# 1_WiFi_POWER.net
KiCad netlist of a schematic drawn in Altium Designer
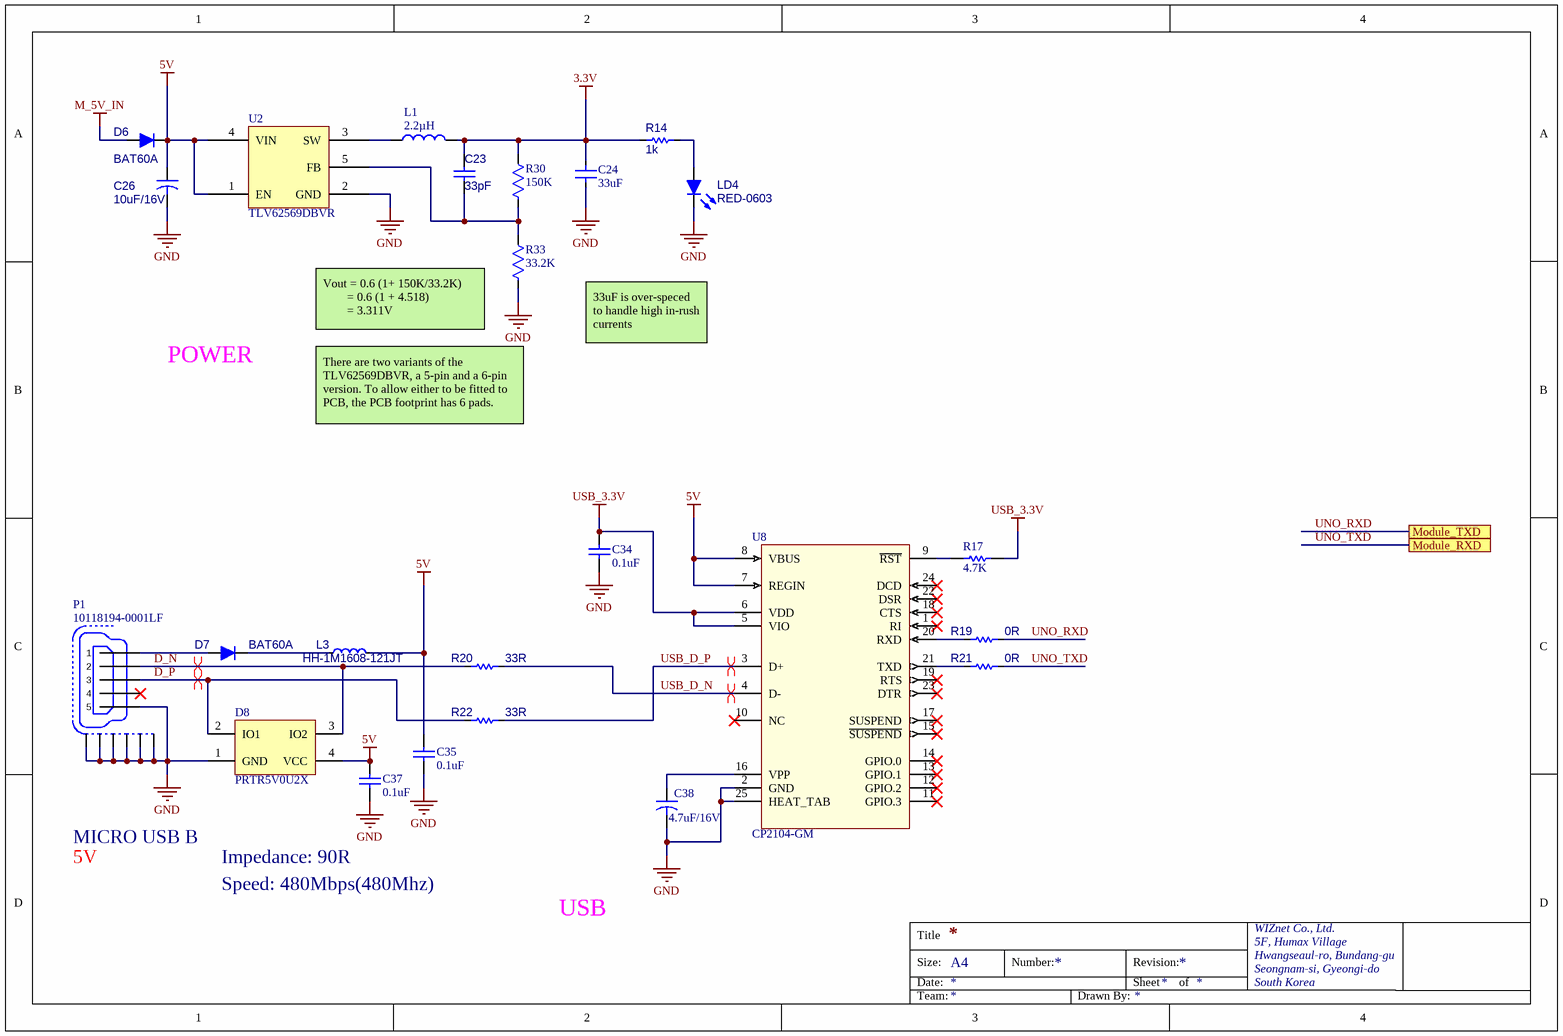
[diagram p0: 1.WiFi_POWER.SchDoc]

(export (version "E")
  (design (tool "Eeschema 10.0.6"))
  (components
    (comp (ref "C23")
      (value "33pF")
      (footprint "CAP-0402")
      (description "Ceramic CAP 0402(1005)")
      (libsource (lib "Scott_lib") (part "CAP-0402"))
    )
    (comp (ref "C24")
      (value "33uF")
      (footprint "CAP-0805")
      (description "0805 10V 33uF X5R 20%")
      (fields
        (field (name "MANUFACTURER") "TDK")
        (field (name "MANUFACTURER PART NUMBER") "C2012X5R0J336M125AC")
      )
      (libsource (lib "TDK_Capacitor_C_0805") (part "33uF 0805 X5R 6.3V"))
    )
    (comp (ref "C26")
      (value "10uF/16V")
      (footprint "CAP-A Size")
      (description "Tantal CAP A Size EIA/IECQ 3216")
      (libsource (lib "Scott_lib") (part "CAP-A Size"))
    )
    (comp (ref "C34")
      (value "0.1uF")
      (footprint "CAP-0402")
      (description "Ceramic CAP 0402(1005)")
      (libsource (lib "Edward") (part "CAP-0402"))
    )
    (comp (ref "C35")
      (value "0.1uF")
      (footprint "CAP-0402")
      (description "Ceramic CAP 0402(1005)")
      (libsource (lib "Edward") (part "CAP-0402"))
    )
    (comp (ref "C37")
      (value "0.1uF")
      (footprint "CAP-0402")
      (description "Ceramic CAP 0402(1005)")
      (libsource (lib "Edward") (part "CAP-0402"))
    )
    (comp (ref "C38")
      (value "4.7uF/16V")
      (footprint "CAP-A Size")
      (description "Tantla CAP A Size EIA/IECQ 3216")
      (libsource (lib "Scott_lib") (part "CAP-A Size"))
    )
    (comp (ref "D6")
      (value "BAT60A")
      (footprint "SOD-323(1-C,2-A)")
      (description "Silicon Schottky Diode")
      (libsource (lib "Scott_lib") (part "DIODE-BAT60A"))
    )
    (comp (ref "D7")
      (value "BAT60A")
      (footprint "SOD-323(1-C,2-A)")
      (description "Silicon Schottky Diode")
      (libsource (lib "Scott_lib") (part "DIODE-BAT60A"))
    )
    (comp (ref "D8")
      (value "PRTR5V0U2X")
      (footprint "SOT-143")
      (description "Ultra low capacitance double rail-to-rail ESD protection diode")
      (fields
        (field (name "MANUFACTURER") "NXP")
        (field (name "2ND SOURCE PART NUMBER") "152-4157")
        (field (name "PUBLISHER") "Nordic Semiconductor")
      )
      (libsource (lib "Quectel_IF_Board") (part "PRTR5V0U2X"))
    )
    (comp (ref "L1")
      (value "2.2µH")
      (footprint "NR3015")
      (description "FIXED IND 2.2UH 1.5A 72 MOHM SMD")
      (fields
        (field (name "MANUFACTURER") "Taiyo Yuden")
        (field (name "MANUFACTURER PART NUMBER") "NR3015T2R2M")
      )
      (libsource (lib "TaiyoYuden ") (part "NR3015T2R2M"))
    )
    (comp (ref "L3")
      (value "HH-1M1608-121JT")
      (footprint "IND-0603")
      (description "Inductor 0603(1608)")
      (libsource (lib "Scott_lib") (part "IND-0603"))
    )
    (comp (ref "LD4")
      (value "RED-0603")
      (footprint "LED-0603-RED")
      (description "LED-0603")
      (libsource (lib "Scott_lib") (part "LED-0603"))
    )
    (comp (ref "P1")
      (value "10118194-0001LF")
      (footprint "USB-FCI-10118194")
      (description "MICRO USB B Type")
      (libsource (lib "Edward") (part "47346-0001"))
    )
    (comp (ref "R14")
      (value "1k")
      (footprint "RES-0402")
      (description "RES-0402")
      (libsource (lib "Edward") (part "RES-0402"))
    )
    (comp (ref "R17")
      (value "4.7K")
      (footprint "RES-0402")
      (description "RES-0402")
      (libsource (lib "") (part "RES-0402_1"))
    )
    (comp (ref "R19")
      (value "0R")
      (footprint "RES-0402")
      (description "RES-0402")
      (libsource (lib "Scott_lib") (part "RES-0402"))
    )
    (comp (ref "R20")
      (value "33R")
      (footprint "RES-0402")
      (description "RES-0402")
      (libsource (lib "Scott_lib") (part "RES-0402"))
    )
    (comp (ref "R21")
      (value "0R")
      (footprint "RES-0402")
      (description "RES-0402")
      (libsource (lib "Scott_lib") (part "RES-0402"))
    )
    (comp (ref "R22")
      (value "33R")
      (footprint "RES-0402")
      (description "RES-0402")
      (libsource (lib "Scott_lib") (part "RES-0402"))
    )
    (comp (ref "R30")
      (value "150K")
      (footprint "RES-0402")
      (description "RES 150K OHM 1/10W 1% 0402 SMD")
      (fields
        (field (name "MANUFACTURER") "Panasonic Electronic Components")
        (field (name "MANUFACTURER PART NUMBER") "ERJ-2RKF1503X")
        (field (name "RESISTANCE (OHMS)") "150K")
      )
      (libsource (lib "Panasonic_Resistor_ERJ2R") (part "150K"))
    )
    (comp (ref "R33")
      (value "33.2K")
      (footprint "RES-0402")
      (description "RES 33.2K OHM 1/10W 1% 0402 SMD")
      (fields
        (field (name "MANUFACTURER") "Panasonic Electronic Components")
        (field (name "MANUFACTURER PART NUMBER") "ERJ-2RKF3322X")
        (field (name "RESISTANCE (OHMS)") "33.2K")
      )
      (libsource (lib "Panasonic_Resistor_ERJ2R") (part "33.2K"))
    )
    (comp (ref "U2")
      (value "TLV62569DBVR")
      (footprint "SOT-23-5L")
      (description "Variable voltage buck converter")
      (fields (field (name "MANUFACTURER") "Texas Instruments"))
      (libsource (lib "TexasInstruments") (part "TLV62569DBVR"))
    )
    (comp (ref "U8")
      (value "CP2104-GM")
      (footprint "QFN24(0.5/4X4)")
      (description "USB to UART Bridge, SiliconLabs")
      (libsource (lib "Edward") (part "CP2104-GM"))
    )
  )
  (nets
    (net (code "1") (name "/D_N") (class "Default")
      (node (ref "D8") (pin "3") (pinfunction "IO2_3") (pintype "passive"))
      (node (ref "P1") (pin "2") (pinfunction "2_2") (pintype "passive"))
      (node (ref "R20") (pin "2") (pinfunction "2_2") (pintype "passive"))
    )
    (net (code "2") (name "/D_P") (class "Default")
      (node (ref "D8") (pin "2") (pinfunction "IO1_2") (pintype "passive"))
      (node (ref "P1") (pin "3") (pinfunction "3_3") (pintype "passive"))
      (node (ref "R22") (pin "2") (pinfunction "2_2") (pintype "passive"))
    )
    (net (code "3") (name "/UNO_RXD") (class "Default")
      (node (ref "R19") (pin "1") (pinfunction "1_1") (pintype "passive"))
    )
    (net (code "4") (name "/UNO_TXD") (class "Default")
      (node (ref "R21") (pin "1") (pinfunction "1_1") (pintype "passive"))
    )
    (net (code "5") (name "/USB_D_N") (class "Default")
      (node (ref "R20") (pin "1") (pinfunction "1_1") (pintype "passive"))
      (node (ref "U8") (pin "4") (pinfunction "D-_4") (pintype "passive"))
    )
    (net (code "6") (name "/USB_D_P") (class "Default")
      (node (ref "R22") (pin "1") (pinfunction "1_1") (pintype "passive"))
      (node (ref "U8") (pin "3") (pinfunction "D+_3") (pintype "passive"))
    )
    (net (code "7") (name "3.3V") (class "Default")
      (node (ref "C23") (pin "2") (pinfunction "2_2") (pintype "passive"))
      (node (ref "C24") (pin "2") (pinfunction "2_2") (pintype "passive"))
      (node (ref "L1") (pin "2") (pinfunction "2_2") (pintype "passive"))
      (node (ref "R14") (pin "1") (pinfunction "1_1") (pintype "passive"))
      (node (ref "R30") (pin "1") (pinfunction "1_1") (pintype "passive"))
    )
    (net (code "8") (name "5V") (class "Default")
      (node (ref "C26") (pin "1") (pinfunction "1_1") (pintype "passive"))
      (node (ref "C35") (pin "2") (pinfunction "2_2") (pintype "passive"))
      (node (ref "C37") (pin "2") (pinfunction "2_2") (pintype "passive"))
      (node (ref "D6") (pin "1") (pinfunction "K_1") (pintype "passive"))
      (node (ref "D8") (pin "4") (pinfunction "VCC_4") (pintype "passive"))
      (node (ref "L3") (pin "2") (pinfunction "2_2") (pintype "passive"))
      (node (ref "U2") (pin "1") (pinfunction "EN_1") (pintype "passive"))
      (node (ref "U2") (pin "4") (pinfunction "VIN_4") (pintype "passive"))
      (node (ref "U8") (pin "7") (pinfunction "REGIN_7") (pintype "input"))
      (node (ref "U8") (pin "8") (pinfunction "VBUS_8") (pintype "input"))
    )
    (net (code "9") (name "GND") (class "Default")
      (node (ref "C24") (pin "1") (pinfunction "1_1") (pintype "passive"))
      (node (ref "C26") (pin "2") (pinfunction "2_2") (pintype "passive"))
      (node (ref "C34") (pin "1") (pinfunction "1_1") (pintype "passive"))
      (node (ref "C35") (pin "1") (pinfunction "1_1") (pintype "passive"))
      (node (ref "C37") (pin "1") (pinfunction "1_1") (pintype "passive"))
      (node (ref "C38") (pin "2") (pinfunction "2_2") (pintype "passive"))
      (node (ref "D8") (pin "1") (pinfunction "GND_1") (pintype "passive"))
      (node (ref "LD4") (pin "2") (pinfunction "K_2") (pintype "passive"))
      (node (ref "P1") (pin "10") (pinfunction "10_10") (pintype "passive"))
      (node (ref "P1") (pin "11") (pinfunction "11_11") (pintype "passive"))
      (node (ref "P1") (pin "5") (pinfunction "5_5") (pintype "passive"))
      (node (ref "P1") (pin "6") (pinfunction "6_6") (pintype "passive"))
      (node (ref "P1") (pin "7") (pinfunction "7_7") (pintype "passive"))
      (node (ref "P1") (pin "8") (pinfunction "8_8") (pintype "passive"))
      (node (ref "P1") (pin "9") (pinfunction "9_9") (pintype "passive"))
      (node (ref "R33") (pin "2") (pinfunction "2_2") (pintype "passive"))
      (node (ref "U2") (pin "2") (pinfunction "GND_2") (pintype "passive"))
      (node (ref "U8") (pin "2") (pinfunction "GND_2") (pintype "power_in"))
      (node (ref "U8") (pin "25") (pinfunction "HEAT_TAB_25") (pintype "passive"))
    )
    (net (code "10") (name "M_5V_IN") (class "Default")
      (node (ref "D6") (pin "2") (pinfunction "A_2") (pintype "passive"))
    )
    (net (code "11") (name "Net-(D7-A)") (class "Default")
      (node (ref "D7") (pin "2") (pinfunction "A_2") (pintype "passive"))
      (node (ref "P1") (pin "1") (pinfunction "1_1") (pintype "passive"))
    )
    (net (code "12") (name "Net-(D7-K)") (class "Default")
      (node (ref "D7") (pin "1") (pinfunction "K_1") (pintype "passive"))
      (node (ref "L3") (pin "1") (pinfunction "1_1") (pintype "passive"))
    )
    (net (code "13") (name "Net-(LD4-A)") (class "Default")
      (node (ref "LD4") (pin "1") (pinfunction "A_1") (pintype "passive"))
      (node (ref "R14") (pin "2") (pinfunction "2_2") (pintype "passive"))
    )
    (net (code "14") (name "Net-(U2-FB)") (class "Default")
      (node (ref "C23") (pin "1") (pinfunction "1_1") (pintype "passive"))
      (node (ref "R30") (pin "2") (pinfunction "2_2") (pintype "passive"))
      (node (ref "R33") (pin "1") (pinfunction "1_1") (pintype "passive"))
      (node (ref "U2") (pin "5") (pinfunction "FB_5") (pintype "passive"))
    )
    (net (code "15") (name "Net-(U2-SW)") (class "Default")
      (node (ref "L1") (pin "1") (pinfunction "1_1") (pintype "passive"))
      (node (ref "U2") (pin "3") (pinfunction "SW_3") (pintype "passive"))
    )
    (net (code "16") (name "Net-(U8-RST)") (class "Default")
      (node (ref "R17") (pin "1") (pinfunction "1_1") (pintype "passive"))
      (node (ref "U8") (pin "9") (pinfunction "RST_9") (pintype "passive"))
    )
    (net (code "17") (name "Net-(U8-RXD)") (class "Default")
      (node (ref "R19") (pin "2") (pinfunction "2_2") (pintype "passive"))
      (node (ref "U8") (pin "20") (pinfunction "RXD_20") (pintype "input"))
    )
    (net (code "18") (name "Net-(U8-TXD)") (class "Default")
      (node (ref "R21") (pin "2") (pinfunction "2_2") (pintype "passive"))
      (node (ref "U8") (pin "21") (pinfunction "TXD_21") (pintype "output"))
    )
    (net (code "19") (name "Net-(U8-VPP)") (class "Default")
      (node (ref "C38") (pin "1") (pinfunction "1_1") (pintype "passive"))
      (node (ref "U8") (pin "16") (pinfunction "VPP_16") (pintype "passive"))
    )
    (net (code "20") (name "USB_3.3V") (class "Default")
      (node (ref "C34") (pin "2") (pinfunction "2_2") (pintype "passive"))
      (node (ref "R17") (pin "2") (pinfunction "2_2") (pintype "passive"))
      (node (ref "U8") (pin "5") (pinfunction "VIO_5") (pintype "power_in"))
      (node (ref "U8") (pin "6") (pinfunction "VDD_6") (pintype "power_in"))
    )
    (net (code "21") (name "unconnected-(P1-Pad4)") (class "Default")
      (node (ref "P1") (pin "4") (pinfunction "4_4") (pintype "passive+no_connect"))
    )
    (net (code "22") (name "unconnected-(U8-CTS-Pad18)") (class "Default")
      (node (ref "U8") (pin "18") (pinfunction "CTS_18") (pintype "input+no_connect"))
    )
    (net (code "23") (name "unconnected-(U8-DCD-Pad24)") (class "Default")
      (node (ref "U8") (pin "24") (pinfunction "DCD_24") (pintype "input+no_connect"))
    )
    (net (code "24") (name "unconnected-(U8-DSR-Pad22)") (class "Default")
      (node (ref "U8") (pin "22") (pinfunction "DSR_22") (pintype "input+no_connect"))
    )
    (net (code "25") (name "unconnected-(U8-DTR-Pad23)") (class "Default")
      (node (ref "U8") (pin "23") (pinfunction "DTR_23") (pintype "output+no_connect"))
    )
    (net (code "26") (name "unconnected-(U8-GPIO.0-Pad14)") (class "Default")
      (node (ref "U8") (pin "14") (pinfunction "GPIO.0_14") (pintype "passive+no_connect"))
    )
    (net (code "27") (name "unconnected-(U8-GPIO.1-Pad13)") (class "Default")
      (node (ref "U8") (pin "13") (pinfunction "GPIO.1_13") (pintype "passive+no_connect"))
    )
    (net (code "28") (name "unconnected-(U8-GPIO.2-Pad12)") (class "Default")
      (node (ref "U8") (pin "12") (pinfunction "GPIO.2_12") (pintype "passive+no_connect"))
    )
    (net (code "29") (name "unconnected-(U8-GPIO.3-Pad11)") (class "Default")
      (node (ref "U8") (pin "11") (pinfunction "GPIO.3_11") (pintype "passive+no_connect"))
    )
    (net (code "30") (name "unconnected-(U8-NC-Pad10)") (class "Default")
      (node (ref "U8") (pin "10") (pinfunction "NC_10") (pintype "passive+no_connect"))
    )
    (net (code "31") (name "unconnected-(U8-RI-Pad1)") (class "Default")
      (node (ref "U8") (pin "1") (pinfunction "RI_1") (pintype "input+no_connect"))
    )
    (net (code "32") (name "unconnected-(U8-RTS-Pad19)") (class "Default")
      (node (ref "U8") (pin "19") (pinfunction "RTS_19") (pintype "output+no_connect"))
    )
    (net (code "33") (name "unconnected-(U8-SUSPEND-Pad15)") (class "Default")
      (node (ref "U8") (pin "15") (pinfunction "SUSPEND_15") (pintype "output+no_connect"))
    )
    (net (code "34") (name "unconnected-(U8-SUSPEND-Pad17)") (class "Default")
      (node (ref "U8") (pin "17") (pinfunction "SUSPEND_17") (pintype "output+no_connect"))
    )
  )
)
